# bandpass_module.net
KiCad netlist of a schematic drawn in EAGLE
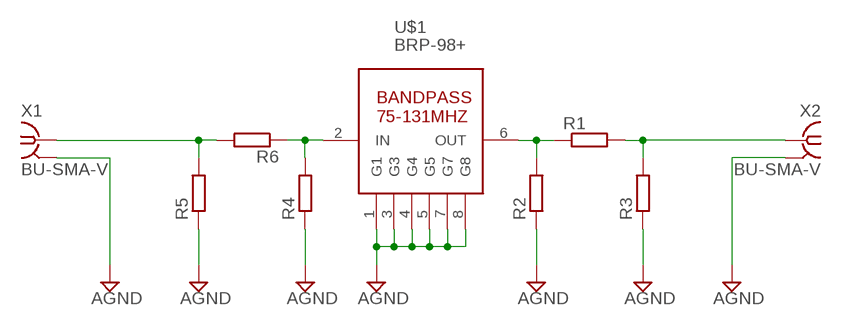
[diagram p0: schematic, sheet 1]

(export (version "E")
  (design (tool "Eeschema 10.0.6"))
  (components
    (comp (ref "R1")
      (value "R-EU_R0805")
      (footprint "eagle-import:R0805")
      (libsource (lib "eagle-import") (part "R-EU_R0805"))
    )
    (comp (ref "R2")
      (value "R-EU_R0805")
      (footprint "eagle-import:R0805")
      (libsource (lib "eagle-import") (part "R-EU_R0805"))
    )
    (comp (ref "R3")
      (value "R-EU_R0805")
      (footprint "eagle-import:R0805")
      (libsource (lib "eagle-import") (part "R-EU_R0805"))
    )
    (comp (ref "R4")
      (value "R-EU_R0805")
      (footprint "eagle-import:R0805")
      (libsource (lib "eagle-import") (part "R-EU_R0805"))
    )
    (comp (ref "R5")
      (value "R-EU_R0805")
      (footprint "eagle-import:R0805")
      (libsource (lib "eagle-import") (part "R-EU_R0805"))
    )
    (comp (ref "R6")
      (value "R-EU_R0805")
      (footprint "eagle-import:R0805")
      (libsource (lib "eagle-import") (part "R-EU_R0805"))
    )
    (comp (ref "U$1")
      (value "BRP-98+")
      (footprint "eagle-import:RBP-98+")
      (libsource (lib "eagle-import") (part "BRP-98+"))
    )
    (comp (ref "X1")
      (value "BU-SMA-V")
      (footprint "eagle-import:BU-SMA-V")
      (libsource (lib "eagle-import") (part "BU-SMA-V"))
    )
    (comp (ref "X2")
      (value "BU-SMA-V")
      (footprint "eagle-import:BU-SMA-V")
      (libsource (lib "eagle-import") (part "BU-SMA-V"))
    )
  )
  (nets
    (net (code "1") (name "AGND") (class "Default")
      (node (ref "R2") (pin "1") (pinfunction "1_1") (pintype "passive"))
      (node (ref "R3") (pin "1") (pinfunction "1_1") (pintype "passive"))
      (node (ref "R4") (pin "1") (pinfunction "1_1") (pintype "passive"))
      (node (ref "R5") (pin "1") (pinfunction "1_1") (pintype "passive"))
      (node (ref "U$1") (pin "1") (pinfunction "G1_1") (pintype "bidirectional"))
      (node (ref "U$1") (pin "3") (pinfunction "G3_3") (pintype "bidirectional"))
      (node (ref "U$1") (pin "4") (pinfunction "G4_4") (pintype "bidirectional"))
      (node (ref "U$1") (pin "5") (pinfunction "G5_5") (pintype "bidirectional"))
      (node (ref "U$1") (pin "7") (pinfunction "G7_7") (pintype "bidirectional"))
      (node (ref "U$1") (pin "8") (pinfunction "G8_8") (pintype "bidirectional"))
      (node (ref "X1") (pin "2") (pinfunction "2_2") (pintype "passive"))
      (node (ref "X1") (pin "3") (pinfunction "2_3") (pintype "passive"))
      (node (ref "X1") (pin "4") (pinfunction "2_4") (pintype "passive"))
      (node (ref "X1") (pin "5") (pinfunction "2_5") (pintype "passive"))
      (node (ref "X2") (pin "2") (pinfunction "2_2") (pintype "passive"))
      (node (ref "X2") (pin "3") (pinfunction "2_3") (pintype "passive"))
      (node (ref "X2") (pin "4") (pinfunction "2_4") (pintype "passive"))
      (node (ref "X2") (pin "5") (pinfunction "2_5") (pintype "passive"))
    )
    (net (code "2") (name "Net-(R1-Pad2)") (class "Default")
      (node (ref "R1") (pin "2") (pinfunction "2_2") (pintype "passive"))
      (node (ref "R3") (pin "2") (pinfunction "2_2") (pintype "passive"))
      (node (ref "X2") (pin "1") (pinfunction "1_1") (pintype "passive"))
    )
    (net (code "3") (name "Net-(R5-Pad2)") (class "Default")
      (node (ref "R5") (pin "2") (pinfunction "2_2") (pintype "passive"))
      (node (ref "R6") (pin "2") (pinfunction "2_2") (pintype "passive"))
      (node (ref "X1") (pin "1") (pinfunction "1_1") (pintype "passive"))
    )
    (net (code "4") (name "Net-(U$1-IN)") (class "Default")
      (node (ref "R4") (pin "2") (pinfunction "2_2") (pintype "passive"))
      (node (ref "R6") (pin "1") (pinfunction "1_1") (pintype "passive"))
      (node (ref "U$1") (pin "2") (pinfunction "IN_2") (pintype "bidirectional"))
    )
    (net (code "5") (name "Net-(U$1-OUT)") (class "Default")
      (node (ref "R1") (pin "1") (pinfunction "1_1") (pintype "passive"))
      (node (ref "R2") (pin "2") (pinfunction "2_2") (pintype "passive"))
      (node (ref "U$1") (pin "6") (pinfunction "OUT_6") (pintype "bidirectional"))
    )
  )
)
